# WS2812_MATRIX_5.net
KiCad netlist of a schematic drawn in Altium Designer
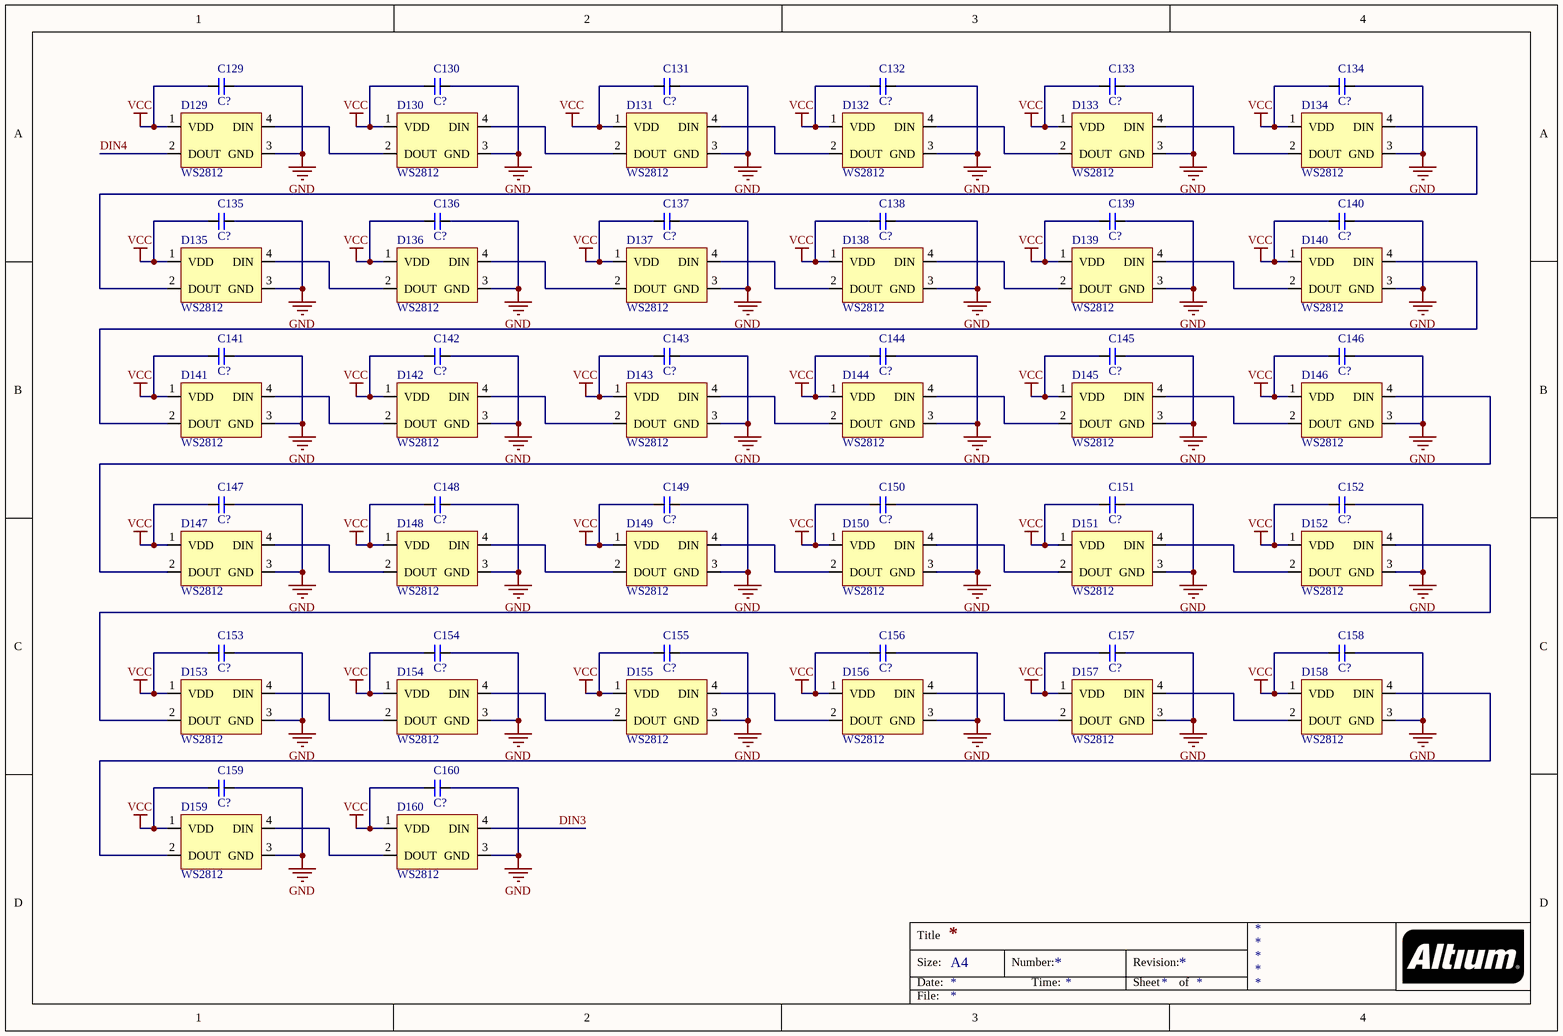
[diagram p0: WS2812_MATRIX_5.SchDoc]

(export (version "E")
  (design (tool "Eeschema 10.0.6"))
  (components
    (comp (ref "C129")
      (value "C?")
      (footprint "C0603")
      (description "Cap")
      (libsource (lib "SCH_Bacsic") (part "CAP"))
    )
    (comp (ref "C130")
      (value "C?")
      (footprint "C0603")
      (description "Cap")
      (libsource (lib "SCH_Bacsic") (part "CAP"))
    )
    (comp (ref "C131")
      (value "C?")
      (footprint "C0603")
      (description "Cap")
      (libsource (lib "SCH_Bacsic") (part "CAP"))
    )
    (comp (ref "C132")
      (value "C?")
      (footprint "C0603")
      (description "Cap")
      (libsource (lib "SCH_Bacsic") (part "CAP"))
    )
    (comp (ref "C133")
      (value "C?")
      (footprint "C0603")
      (description "Cap")
      (libsource (lib "SCH_Bacsic") (part "CAP"))
    )
    (comp (ref "C134")
      (value "C?")
      (footprint "C0603")
      (description "Cap")
      (libsource (lib "SCH_Bacsic") (part "CAP"))
    )
    (comp (ref "C135")
      (value "C?")
      (footprint "C0603")
      (description "Cap")
      (libsource (lib "SCH_Bacsic") (part "CAP"))
    )
    (comp (ref "C136")
      (value "C?")
      (footprint "C0603")
      (description "Cap")
      (libsource (lib "SCH_Bacsic") (part "CAP"))
    )
    (comp (ref "C137")
      (value "C?")
      (footprint "C0603")
      (description "Cap")
      (libsource (lib "SCH_Bacsic") (part "CAP"))
    )
    (comp (ref "C138")
      (value "C?")
      (footprint "C0603")
      (description "Cap")
      (libsource (lib "SCH_Bacsic") (part "CAP"))
    )
    (comp (ref "C139")
      (value "C?")
      (footprint "C0603")
      (description "Cap")
      (libsource (lib "SCH_Bacsic") (part "CAP"))
    )
    (comp (ref "C140")
      (value "C?")
      (footprint "C0603")
      (description "Cap")
      (libsource (lib "SCH_Bacsic") (part "CAP"))
    )
    (comp (ref "C141")
      (value "C?")
      (footprint "C0603")
      (description "Cap")
      (libsource (lib "SCH_Bacsic") (part "CAP"))
    )
    (comp (ref "C142")
      (value "C?")
      (footprint "C0603")
      (description "Cap")
      (libsource (lib "SCH_Bacsic") (part "CAP"))
    )
    (comp (ref "C143")
      (value "C?")
      (footprint "C0603")
      (description "Cap")
      (libsource (lib "SCH_Bacsic") (part "CAP"))
    )
    (comp (ref "C144")
      (value "C?")
      (footprint "C0603")
      (description "Cap")
      (libsource (lib "SCH_Bacsic") (part "CAP"))
    )
    (comp (ref "C145")
      (value "C?")
      (footprint "C0603")
      (description "Cap")
      (libsource (lib "SCH_Bacsic") (part "CAP"))
    )
    (comp (ref "C146")
      (value "C?")
      (footprint "C0603")
      (description "Cap")
      (libsource (lib "SCH_Bacsic") (part "CAP"))
    )
    (comp (ref "C147")
      (value "C?")
      (footprint "C0603")
      (description "Cap")
      (libsource (lib "SCH_Bacsic") (part "CAP"))
    )
    (comp (ref "C148")
      (value "C?")
      (footprint "C0603")
      (description "Cap")
      (libsource (lib "SCH_Bacsic") (part "CAP"))
    )
    (comp (ref "C149")
      (value "C?")
      (footprint "C0603")
      (description "Cap")
      (libsource (lib "SCH_Bacsic") (part "CAP"))
    )
    (comp (ref "C150")
      (value "C?")
      (footprint "C0603")
      (description "Cap")
      (libsource (lib "SCH_Bacsic") (part "CAP"))
    )
    (comp (ref "C151")
      (value "C?")
      (footprint "C0603")
      (description "Cap")
      (libsource (lib "SCH_Bacsic") (part "CAP"))
    )
    (comp (ref "C152")
      (value "C?")
      (footprint "C0603")
      (description "Cap")
      (libsource (lib "SCH_Bacsic") (part "CAP"))
    )
    (comp (ref "C153")
      (value "C?")
      (footprint "C0603")
      (description "Cap")
      (libsource (lib "SCH_Bacsic") (part "CAP"))
    )
    (comp (ref "C154")
      (value "C?")
      (footprint "C0603")
      (description "Cap")
      (libsource (lib "SCH_Bacsic") (part "CAP"))
    )
    (comp (ref "C155")
      (value "C?")
      (footprint "C0603")
      (description "Cap")
      (libsource (lib "SCH_Bacsic") (part "CAP"))
    )
    (comp (ref "C156")
      (value "C?")
      (footprint "C0603")
      (description "Cap")
      (libsource (lib "SCH_Bacsic") (part "CAP"))
    )
    (comp (ref "C157")
      (value "C?")
      (footprint "C0603")
      (description "Cap")
      (libsource (lib "SCH_Bacsic") (part "CAP"))
    )
    (comp (ref "C158")
      (value "C?")
      (footprint "C0603")
      (description "Cap")
      (libsource (lib "SCH_Bacsic") (part "CAP"))
    )
    (comp (ref "C159")
      (value "C?")
      (footprint "C0603")
      (description "Cap")
      (libsource (lib "SCH_Bacsic") (part "CAP"))
    )
    (comp (ref "C160")
      (value "C?")
      (footprint "C0603")
      (description "Cap")
      (libsource (lib "SCH_Bacsic") (part "CAP"))
    )
    (comp (ref "D129")
      (value "WS2812")
      (footprint "WS2812_3528")
      (libsource (lib "SCH_Bacsic") (part "WS2812"))
    )
    (comp (ref "D130")
      (value "WS2812")
      (footprint "WS2812_3528")
      (libsource (lib "SCH_Bacsic") (part "WS2812"))
    )
    (comp (ref "D131")
      (value "WS2812")
      (footprint "WS2812_3528")
      (libsource (lib "SCH_Bacsic") (part "WS2812"))
    )
    (comp (ref "D132")
      (value "WS2812")
      (footprint "WS2812_3528")
      (libsource (lib "SCH_Bacsic") (part "WS2812"))
    )
    (comp (ref "D133")
      (value "WS2812")
      (footprint "WS2812_3528")
      (libsource (lib "SCH_Bacsic") (part "WS2812"))
    )
    (comp (ref "D134")
      (value "WS2812")
      (footprint "WS2812_3528")
      (libsource (lib "SCH_Bacsic") (part "WS2812"))
    )
    (comp (ref "D135")
      (value "WS2812")
      (footprint "WS2812_3528")
      (libsource (lib "SCH_Bacsic") (part "WS2812"))
    )
    (comp (ref "D136")
      (value "WS2812")
      (footprint "WS2812_3528")
      (libsource (lib "SCH_Bacsic") (part "WS2812"))
    )
    (comp (ref "D137")
      (value "WS2812")
      (footprint "WS2812_3528")
      (libsource (lib "SCH_Bacsic") (part "WS2812"))
    )
    (comp (ref "D138")
      (value "WS2812")
      (footprint "WS2812_3528")
      (libsource (lib "SCH_Bacsic") (part "WS2812"))
    )
    (comp (ref "D139")
      (value "WS2812")
      (footprint "WS2812_3528")
      (libsource (lib "SCH_Bacsic") (part "WS2812"))
    )
    (comp (ref "D140")
      (value "WS2812")
      (footprint "WS2812_3528")
      (libsource (lib "SCH_Bacsic") (part "WS2812"))
    )
    (comp (ref "D141")
      (value "WS2812")
      (footprint "WS2812_3528")
      (libsource (lib "SCH_Bacsic") (part "WS2812"))
    )
    (comp (ref "D142")
      (value "WS2812")
      (footprint "WS2812_3528")
      (libsource (lib "SCH_Bacsic") (part "WS2812"))
    )
    (comp (ref "D143")
      (value "WS2812")
      (footprint "WS2812_3528")
      (libsource (lib "SCH_Bacsic") (part "WS2812"))
    )
    (comp (ref "D144")
      (value "WS2812")
      (footprint "WS2812_3528")
      (libsource (lib "SCH_Bacsic") (part "WS2812"))
    )
    (comp (ref "D145")
      (value "WS2812")
      (footprint "WS2812_3528")
      (libsource (lib "SCH_Bacsic") (part "WS2812"))
    )
    (comp (ref "D146")
      (value "WS2812")
      (footprint "WS2812_3528")
      (libsource (lib "SCH_Bacsic") (part "WS2812"))
    )
    (comp (ref "D147")
      (value "WS2812")
      (footprint "WS2812_3528")
      (libsource (lib "SCH_Bacsic") (part "WS2812"))
    )
    (comp (ref "D148")
      (value "WS2812")
      (footprint "WS2812_3528")
      (libsource (lib "SCH_Bacsic") (part "WS2812"))
    )
    (comp (ref "D149")
      (value "WS2812")
      (footprint "WS2812_3528")
      (libsource (lib "SCH_Bacsic") (part "WS2812"))
    )
    (comp (ref "D150")
      (value "WS2812")
      (footprint "WS2812_3528")
      (libsource (lib "SCH_Bacsic") (part "WS2812"))
    )
    (comp (ref "D151")
      (value "WS2812")
      (footprint "WS2812_3528")
      (libsource (lib "SCH_Bacsic") (part "WS2812"))
    )
    (comp (ref "D152")
      (value "WS2812")
      (footprint "WS2812_3528")
      (libsource (lib "SCH_Bacsic") (part "WS2812"))
    )
    (comp (ref "D153")
      (value "WS2812")
      (footprint "WS2812_3528")
      (libsource (lib "SCH_Bacsic") (part "WS2812"))
    )
    (comp (ref "D154")
      (value "WS2812")
      (footprint "WS2812_3528")
      (libsource (lib "SCH_Bacsic") (part "WS2812"))
    )
    (comp (ref "D155")
      (value "WS2812")
      (footprint "WS2812_3528")
      (libsource (lib "SCH_Bacsic") (part "WS2812"))
    )
    (comp (ref "D156")
      (value "WS2812")
      (footprint "WS2812_3528")
      (libsource (lib "SCH_Bacsic") (part "WS2812"))
    )
    (comp (ref "D157")
      (value "WS2812")
      (footprint "WS2812_3528")
      (libsource (lib "SCH_Bacsic") (part "WS2812"))
    )
    (comp (ref "D158")
      (value "WS2812")
      (footprint "WS2812_3528")
      (libsource (lib "SCH_Bacsic") (part "WS2812"))
    )
    (comp (ref "D159")
      (value "WS2812")
      (footprint "WS2812_3528")
      (libsource (lib "SCH_Bacsic") (part "WS2812"))
    )
    (comp (ref "D160")
      (value "WS2812")
      (footprint "WS2812_3528")
      (libsource (lib "SCH_Bacsic") (part "WS2812"))
    )
  )
  (nets
    (net (code "1") (name "/DIN3") (class "Default")
      (node (ref "D160") (pin "4") (pinfunction "DIN_4") (pintype "passive"))
    )
    (net (code "2") (name "/DIN4") (class "Default")
      (node (ref "D129") (pin "2") (pinfunction "DOUT_2") (pintype "passive"))
    )
    (net (code "3") (name "GND") (class "Default")
      (node (ref "C129") (pin "2") (pintype "passive"))
      (node (ref "C130") (pin "2") (pintype "passive"))
      (node (ref "C131") (pin "2") (pintype "passive"))
      (node (ref "C132") (pin "2") (pintype "passive"))
      (node (ref "C133") (pin "2") (pintype "passive"))
      (node (ref "C134") (pin "2") (pintype "passive"))
      (node (ref "C135") (pin "2") (pintype "passive"))
      (node (ref "C136") (pin "2") (pintype "passive"))
      (node (ref "C137") (pin "2") (pintype "passive"))
      (node (ref "C138") (pin "2") (pintype "passive"))
      (node (ref "C139") (pin "2") (pintype "passive"))
      (node (ref "C140") (pin "2") (pintype "passive"))
      (node (ref "C141") (pin "2") (pintype "passive"))
      (node (ref "C142") (pin "2") (pintype "passive"))
      (node (ref "C143") (pin "2") (pintype "passive"))
      (node (ref "C144") (pin "2") (pintype "passive"))
      (node (ref "C145") (pin "2") (pintype "passive"))
      (node (ref "C146") (pin "2") (pintype "passive"))
      (node (ref "C147") (pin "2") (pintype "passive"))
      (node (ref "C148") (pin "2") (pintype "passive"))
      (node (ref "C149") (pin "2") (pintype "passive"))
      (node (ref "C150") (pin "2") (pintype "passive"))
      (node (ref "C151") (pin "2") (pintype "passive"))
      (node (ref "C152") (pin "2") (pintype "passive"))
      (node (ref "C153") (pin "2") (pintype "passive"))
      (node (ref "C154") (pin "2") (pintype "passive"))
      (node (ref "C155") (pin "2") (pintype "passive"))
      (node (ref "C156") (pin "2") (pintype "passive"))
      (node (ref "C157") (pin "2") (pintype "passive"))
      (node (ref "C158") (pin "2") (pintype "passive"))
      (node (ref "C159") (pin "2") (pintype "passive"))
      (node (ref "C160") (pin "2") (pintype "passive"))
      (node (ref "D129") (pin "3") (pinfunction "GND_3") (pintype "passive"))
      (node (ref "D130") (pin "3") (pinfunction "GND_3") (pintype "passive"))
      (node (ref "D131") (pin "3") (pinfunction "GND_3") (pintype "passive"))
      (node (ref "D132") (pin "3") (pinfunction "GND_3") (pintype "passive"))
      (node (ref "D133") (pin "3") (pinfunction "GND_3") (pintype "passive"))
      (node (ref "D134") (pin "3") (pinfunction "GND_3") (pintype "passive"))
      (node (ref "D135") (pin "3") (pinfunction "GND_3") (pintype "passive"))
      (node (ref "D136") (pin "3") (pinfunction "GND_3") (pintype "passive"))
      (node (ref "D137") (pin "3") (pinfunction "GND_3") (pintype "passive"))
      (node (ref "D138") (pin "3") (pinfunction "GND_3") (pintype "passive"))
      (node (ref "D139") (pin "3") (pinfunction "GND_3") (pintype "passive"))
      (node (ref "D140") (pin "3") (pinfunction "GND_3") (pintype "passive"))
      (node (ref "D141") (pin "3") (pinfunction "GND_3") (pintype "passive"))
      (node (ref "D142") (pin "3") (pinfunction "GND_3") (pintype "passive"))
      (node (ref "D143") (pin "3") (pinfunction "GND_3") (pintype "passive"))
      (node (ref "D144") (pin "3") (pinfunction "GND_3") (pintype "passive"))
      (node (ref "D145") (pin "3") (pinfunction "GND_3") (pintype "passive"))
      (node (ref "D146") (pin "3") (pinfunction "GND_3") (pintype "passive"))
      (node (ref "D147") (pin "3") (pinfunction "GND_3") (pintype "passive"))
      (node (ref "D148") (pin "3") (pinfunction "GND_3") (pintype "passive"))
      (node (ref "D149") (pin "3") (pinfunction "GND_3") (pintype "passive"))
      (node (ref "D150") (pin "3") (pinfunction "GND_3") (pintype "passive"))
      (node (ref "D151") (pin "3") (pinfunction "GND_3") (pintype "passive"))
      (node (ref "D152") (pin "3") (pinfunction "GND_3") (pintype "passive"))
      (node (ref "D153") (pin "3") (pinfunction "GND_3") (pintype "passive"))
      (node (ref "D154") (pin "3") (pinfunction "GND_3") (pintype "passive"))
      (node (ref "D155") (pin "3") (pinfunction "GND_3") (pintype "passive"))
      (node (ref "D156") (pin "3") (pinfunction "GND_3") (pintype "passive"))
      (node (ref "D157") (pin "3") (pinfunction "GND_3") (pintype "passive"))
      (node (ref "D158") (pin "3") (pinfunction "GND_3") (pintype "passive"))
      (node (ref "D159") (pin "3") (pinfunction "GND_3") (pintype "passive"))
      (node (ref "D160") (pin "3") (pinfunction "GND_3") (pintype "passive"))
    )
    (net (code "4") (name "Net-(D129-DIN)") (class "Default")
      (node (ref "D129") (pin "4") (pinfunction "DIN_4") (pintype "passive"))
      (node (ref "D130") (pin "2") (pinfunction "DOUT_2") (pintype "passive"))
    )
    (net (code "5") (name "Net-(D130-DIN)") (class "Default")
      (node (ref "D130") (pin "4") (pinfunction "DIN_4") (pintype "passive"))
      (node (ref "D131") (pin "2") (pinfunction "DOUT_2") (pintype "passive"))
    )
    (net (code "6") (name "Net-(D131-DIN)") (class "Default")
      (node (ref "D131") (pin "4") (pinfunction "DIN_4") (pintype "passive"))
      (node (ref "D132") (pin "2") (pinfunction "DOUT_2") (pintype "passive"))
    )
    (net (code "7") (name "Net-(D132-DIN)") (class "Default")
      (node (ref "D132") (pin "4") (pinfunction "DIN_4") (pintype "passive"))
      (node (ref "D133") (pin "2") (pinfunction "DOUT_2") (pintype "passive"))
    )
    (net (code "8") (name "Net-(D133-DIN)") (class "Default")
      (node (ref "D133") (pin "4") (pinfunction "DIN_4") (pintype "passive"))
      (node (ref "D134") (pin "2") (pinfunction "DOUT_2") (pintype "passive"))
    )
    (net (code "9") (name "Net-(D134-DIN)") (class "Default")
      (node (ref "D134") (pin "4") (pinfunction "DIN_4") (pintype "passive"))
      (node (ref "D135") (pin "2") (pinfunction "DOUT_2") (pintype "passive"))
    )
    (net (code "10") (name "Net-(D135-DIN)") (class "Default")
      (node (ref "D135") (pin "4") (pinfunction "DIN_4") (pintype "passive"))
      (node (ref "D136") (pin "2") (pinfunction "DOUT_2") (pintype "passive"))
    )
    (net (code "11") (name "Net-(D136-DIN)") (class "Default")
      (node (ref "D136") (pin "4") (pinfunction "DIN_4") (pintype "passive"))
      (node (ref "D137") (pin "2") (pinfunction "DOUT_2") (pintype "passive"))
    )
    (net (code "12") (name "Net-(D137-DIN)") (class "Default")
      (node (ref "D137") (pin "4") (pinfunction "DIN_4") (pintype "passive"))
      (node (ref "D138") (pin "2") (pinfunction "DOUT_2") (pintype "passive"))
    )
    (net (code "13") (name "Net-(D138-DIN)") (class "Default")
      (node (ref "D138") (pin "4") (pinfunction "DIN_4") (pintype "passive"))
      (node (ref "D139") (pin "2") (pinfunction "DOUT_2") (pintype "passive"))
    )
    (net (code "14") (name "Net-(D139-DIN)") (class "Default")
      (node (ref "D139") (pin "4") (pinfunction "DIN_4") (pintype "passive"))
      (node (ref "D140") (pin "2") (pinfunction "DOUT_2") (pintype "passive"))
    )
    (net (code "15") (name "Net-(D140-DIN)") (class "Default")
      (node (ref "D140") (pin "4") (pinfunction "DIN_4") (pintype "passive"))
      (node (ref "D141") (pin "2") (pinfunction "DOUT_2") (pintype "passive"))
    )
    (net (code "16") (name "Net-(D141-DIN)") (class "Default")
      (node (ref "D141") (pin "4") (pinfunction "DIN_4") (pintype "passive"))
      (node (ref "D142") (pin "2") (pinfunction "DOUT_2") (pintype "passive"))
    )
    (net (code "17") (name "Net-(D142-DIN)") (class "Default")
      (node (ref "D142") (pin "4") (pinfunction "DIN_4") (pintype "passive"))
      (node (ref "D143") (pin "2") (pinfunction "DOUT_2") (pintype "passive"))
    )
    (net (code "18") (name "Net-(D143-DIN)") (class "Default")
      (node (ref "D143") (pin "4") (pinfunction "DIN_4") (pintype "passive"))
      (node (ref "D144") (pin "2") (pinfunction "DOUT_2") (pintype "passive"))
    )
    (net (code "19") (name "Net-(D144-DIN)") (class "Default")
      (node (ref "D144") (pin "4") (pinfunction "DIN_4") (pintype "passive"))
      (node (ref "D145") (pin "2") (pinfunction "DOUT_2") (pintype "passive"))
    )
    (net (code "20") (name "Net-(D145-DIN)") (class "Default")
      (node (ref "D145") (pin "4") (pinfunction "DIN_4") (pintype "passive"))
      (node (ref "D146") (pin "2") (pinfunction "DOUT_2") (pintype "passive"))
    )
    (net (code "21") (name "Net-(D146-DIN)") (class "Default")
      (node (ref "D146") (pin "4") (pinfunction "DIN_4") (pintype "passive"))
      (node (ref "D147") (pin "2") (pinfunction "DOUT_2") (pintype "passive"))
    )
    (net (code "22") (name "Net-(D147-DIN)") (class "Default")
      (node (ref "D147") (pin "4") (pinfunction "DIN_4") (pintype "passive"))
      (node (ref "D148") (pin "2") (pinfunction "DOUT_2") (pintype "passive"))
    )
    (net (code "23") (name "Net-(D148-DIN)") (class "Default")
      (node (ref "D148") (pin "4") (pinfunction "DIN_4") (pintype "passive"))
      (node (ref "D149") (pin "2") (pinfunction "DOUT_2") (pintype "passive"))
    )
    (net (code "24") (name "Net-(D149-DIN)") (class "Default")
      (node (ref "D149") (pin "4") (pinfunction "DIN_4") (pintype "passive"))
      (node (ref "D150") (pin "2") (pinfunction "DOUT_2") (pintype "passive"))
    )
    (net (code "25") (name "Net-(D150-DIN)") (class "Default")
      (node (ref "D150") (pin "4") (pinfunction "DIN_4") (pintype "passive"))
      (node (ref "D151") (pin "2") (pinfunction "DOUT_2") (pintype "passive"))
    )
    (net (code "26") (name "Net-(D151-DIN)") (class "Default")
      (node (ref "D151") (pin "4") (pinfunction "DIN_4") (pintype "passive"))
      (node (ref "D152") (pin "2") (pinfunction "DOUT_2") (pintype "passive"))
    )
    (net (code "27") (name "Net-(D152-DIN)") (class "Default")
      (node (ref "D152") (pin "4") (pinfunction "DIN_4") (pintype "passive"))
      (node (ref "D153") (pin "2") (pinfunction "DOUT_2") (pintype "passive"))
    )
    (net (code "28") (name "Net-(D153-DIN)") (class "Default")
      (node (ref "D153") (pin "4") (pinfunction "DIN_4") (pintype "passive"))
      (node (ref "D154") (pin "2") (pinfunction "DOUT_2") (pintype "passive"))
    )
    (net (code "29") (name "Net-(D154-DIN)") (class "Default")
      (node (ref "D154") (pin "4") (pinfunction "DIN_4") (pintype "passive"))
      (node (ref "D155") (pin "2") (pinfunction "DOUT_2") (pintype "passive"))
    )
    (net (code "30") (name "Net-(D155-DIN)") (class "Default")
      (node (ref "D155") (pin "4") (pinfunction "DIN_4") (pintype "passive"))
      (node (ref "D156") (pin "2") (pinfunction "DOUT_2") (pintype "passive"))
    )
    (net (code "31") (name "Net-(D156-DIN)") (class "Default")
      (node (ref "D156") (pin "4") (pinfunction "DIN_4") (pintype "passive"))
      (node (ref "D157") (pin "2") (pinfunction "DOUT_2") (pintype "passive"))
    )
    (net (code "32") (name "Net-(D157-DIN)") (class "Default")
      (node (ref "D157") (pin "4") (pinfunction "DIN_4") (pintype "passive"))
      (node (ref "D158") (pin "2") (pinfunction "DOUT_2") (pintype "passive"))
    )
    (net (code "33") (name "Net-(D158-DIN)") (class "Default")
      (node (ref "D158") (pin "4") (pinfunction "DIN_4") (pintype "passive"))
      (node (ref "D159") (pin "2") (pinfunction "DOUT_2") (pintype "passive"))
    )
    (net (code "34") (name "Net-(D159-DIN)") (class "Default")
      (node (ref "D159") (pin "4") (pinfunction "DIN_4") (pintype "passive"))
      (node (ref "D160") (pin "2") (pinfunction "DOUT_2") (pintype "passive"))
    )
    (net (code "35") (name "VCC") (class "Default")
      (node (ref "C129") (pin "1") (pintype "passive"))
      (node (ref "C130") (pin "1") (pintype "passive"))
      (node (ref "C131") (pin "1") (pintype "passive"))
      (node (ref "C132") (pin "1") (pintype "passive"))
      (node (ref "C133") (pin "1") (pintype "passive"))
      (node (ref "C134") (pin "1") (pintype "passive"))
      (node (ref "C135") (pin "1") (pintype "passive"))
      (node (ref "C136") (pin "1") (pintype "passive"))
      (node (ref "C137") (pin "1") (pintype "passive"))
      (node (ref "C138") (pin "1") (pintype "passive"))
      (node (ref "C139") (pin "1") (pintype "passive"))
      (node (ref "C140") (pin "1") (pintype "passive"))
      (node (ref "C141") (pin "1") (pintype "passive"))
      (node (ref "C142") (pin "1") (pintype "passive"))
      (node (ref "C143") (pin "1") (pintype "passive"))
      (node (ref "C144") (pin "1") (pintype "passive"))
      (node (ref "C145") (pin "1") (pintype "passive"))
      (node (ref "C146") (pin "1") (pintype "passive"))
      (node (ref "C147") (pin "1") (pintype "passive"))
      (node (ref "C148") (pin "1") (pintype "passive"))
      (node (ref "C149") (pin "1") (pintype "passive"))
      (node (ref "C150") (pin "1") (pintype "passive"))
      (node (ref "C151") (pin "1") (pintype "passive"))
      (node (ref "C152") (pin "1") (pintype "passive"))
      (node (ref "C153") (pin "1") (pintype "passive"))
      (node (ref "C154") (pin "1") (pintype "passive"))
      (node (ref "C155") (pin "1") (pintype "passive"))
      (node (ref "C156") (pin "1") (pintype "passive"))
      (node (ref "C157") (pin "1") (pintype "passive"))
      (node (ref "C158") (pin "1") (pintype "passive"))
      (node (ref "C159") (pin "1") (pintype "passive"))
      (node (ref "C160") (pin "1") (pintype "passive"))
      (node (ref "D129") (pin "1") (pinfunction "VDD_1") (pintype "passive"))
      (node (ref "D130") (pin "1") (pinfunction "VDD_1") (pintype "passive"))
      (node (ref "D131") (pin "1") (pinfunction "VDD_1") (pintype "passive"))
      (node (ref "D132") (pin "1") (pinfunction "VDD_1") (pintype "passive"))
      (node (ref "D133") (pin "1") (pinfunction "VDD_1") (pintype "passive"))
      (node (ref "D134") (pin "1") (pinfunction "VDD_1") (pintype "passive"))
      (node (ref "D135") (pin "1") (pinfunction "VDD_1") (pintype "passive"))
      (node (ref "D136") (pin "1") (pinfunction "VDD_1") (pintype "passive"))
      (node (ref "D137") (pin "1") (pinfunction "VDD_1") (pintype "passive"))
      (node (ref "D138") (pin "1") (pinfunction "VDD_1") (pintype "passive"))
      (node (ref "D139") (pin "1") (pinfunction "VDD_1") (pintype "passive"))
      (node (ref "D140") (pin "1") (pinfunction "VDD_1") (pintype "passive"))
      (node (ref "D141") (pin "1") (pinfunction "VDD_1") (pintype "passive"))
      (node (ref "D142") (pin "1") (pinfunction "VDD_1") (pintype "passive"))
      (node (ref "D143") (pin "1") (pinfunction "VDD_1") (pintype "passive"))
      (node (ref "D144") (pin "1") (pinfunction "VDD_1") (pintype "passive"))
      (node (ref "D145") (pin "1") (pinfunction "VDD_1") (pintype "passive"))
      (node (ref "D146") (pin "1") (pinfunction "VDD_1") (pintype "passive"))
      (node (ref "D147") (pin "1") (pinfunction "VDD_1") (pintype "passive"))
      (node (ref "D148") (pin "1") (pinfunction "VDD_1") (pintype "passive"))
      (node (ref "D149") (pin "1") (pinfunction "VDD_1") (pintype "passive"))
      (node (ref "D150") (pin "1") (pinfunction "VDD_1") (pintype "passive"))
      (node (ref "D151") (pin "1") (pinfunction "VDD_1") (pintype "passive"))
      (node (ref "D152") (pin "1") (pinfunction "VDD_1") (pintype "passive"))
      (node (ref "D153") (pin "1") (pinfunction "VDD_1") (pintype "passive"))
      (node (ref "D154") (pin "1") (pinfunction "VDD_1") (pintype "passive"))
      (node (ref "D155") (pin "1") (pinfunction "VDD_1") (pintype "passive"))
      (node (ref "D156") (pin "1") (pinfunction "VDD_1") (pintype "passive"))
      (node (ref "D157") (pin "1") (pinfunction "VDD_1") (pintype "passive"))
      (node (ref "D158") (pin "1") (pinfunction "VDD_1") (pintype "passive"))
      (node (ref "D159") (pin "1") (pinfunction "VDD_1") (pintype "passive"))
      (node (ref "D160") (pin "1") (pinfunction "VDD_1") (pintype "passive"))
    )
  )
)
